# dc25-darknet-dialer-eaglev8_1.net
KiCad netlist of a schematic drawn in EAGLE
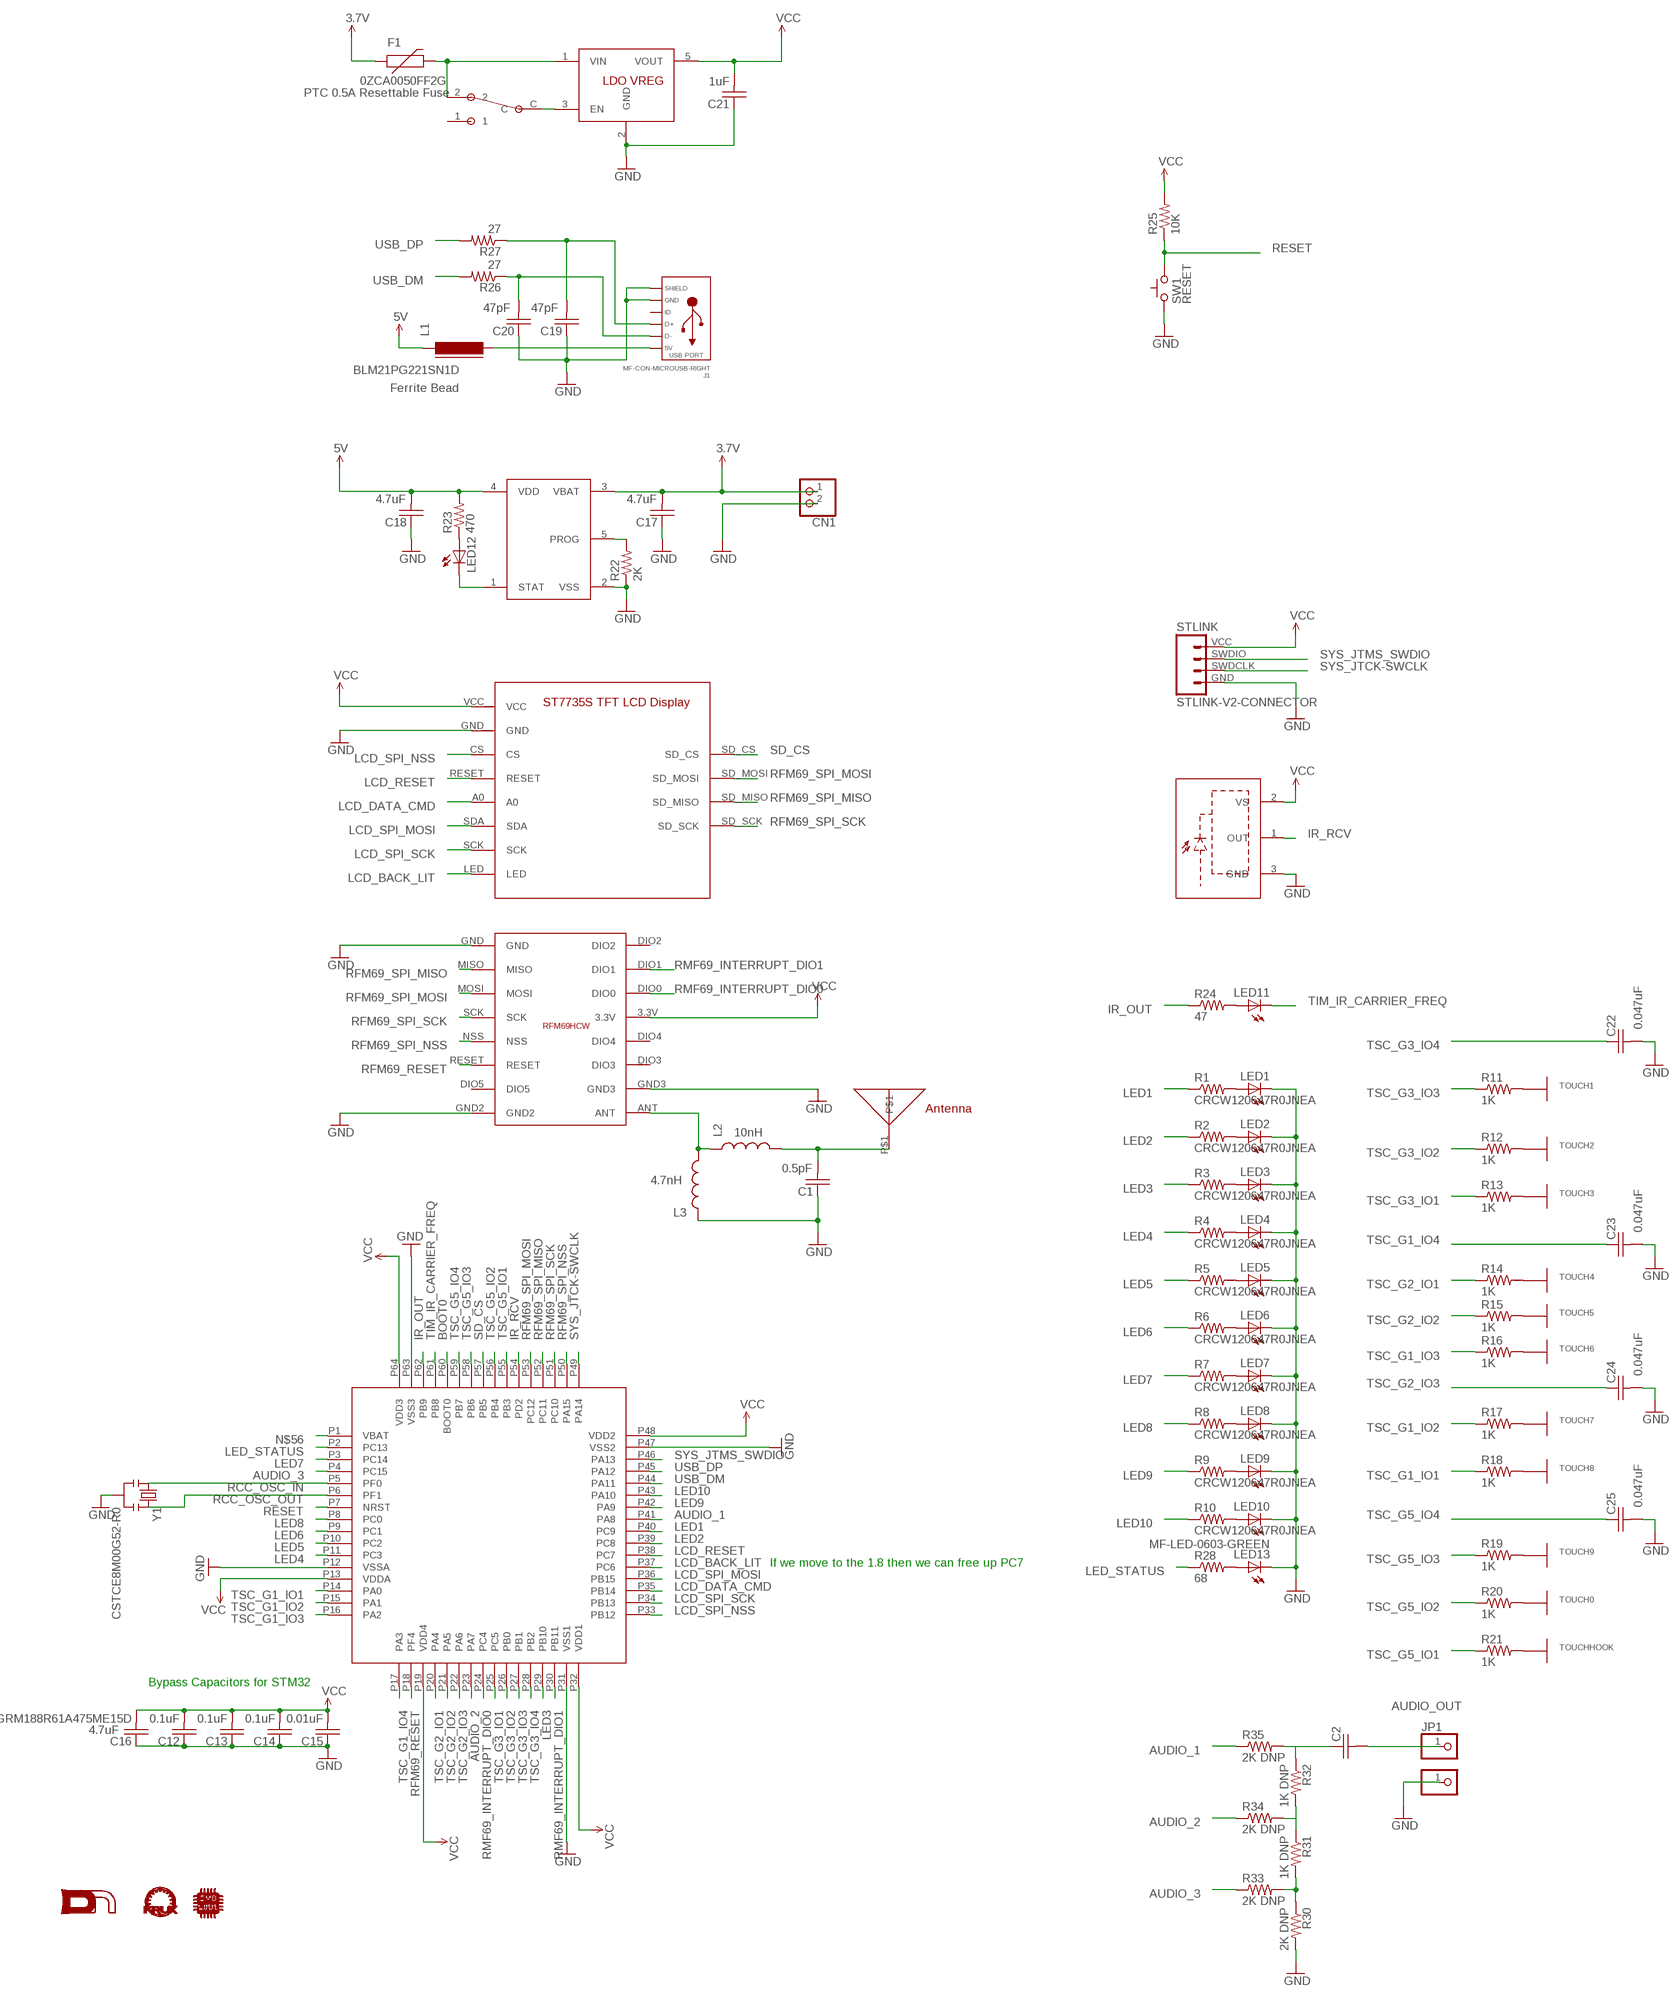
[diagram p0: schematic, sheet 1]

(export (version "E")
  (design (tool "Eeschema 10.0.6"))
  (components
    (comp (ref "C1")
      (value "251R14S0R5BV4T")
      (footprint "eagle-import:C0603")
      (libsource (lib "eagle-import") (part "C-USC0603"))
    )
    (comp (ref "C2")
      (value "10uF DNP")
      (footprint "eagle-import:C0603")
      (libsource (lib "eagle-import") (part "C-USC0603"))
    )
    (comp (ref "C12")
      (value "0.1uF")
      (footprint "eagle-import:C0603")
      (libsource (lib "eagle-import") (part "C-USC0603"))
    )
    (comp (ref "C13")
      (value "0.1uF")
      (footprint "eagle-import:C0603")
      (libsource (lib "eagle-import") (part "C-USC0603"))
    )
    (comp (ref "C14")
      (value "0.1uF")
      (footprint "eagle-import:C0603")
      (libsource (lib "eagle-import") (part "C-USC0603"))
    )
    (comp (ref "C15")
      (value "0.01uF")
      (footprint "eagle-import:C0603")
      (libsource (lib "eagle-import") (part "C-USC0603"))
    )
    (comp (ref "C16")
      (value "GRM188R61A475ME15D")
      (footprint "eagle-import:C0603")
      (libsource (lib "eagle-import") (part "C-USC0603"))
    )
    (comp (ref "C17")
      (value "GRM188R61A475ME15D")
      (footprint "eagle-import:C0603")
      (libsource (lib "eagle-import") (part "C-USC0603"))
    )
    (comp (ref "C18")
      (value "GRM188R61A475ME15D")
      (footprint "eagle-import:C0603")
      (libsource (lib "eagle-import") (part "C-USC0603"))
    )
    (comp (ref "C19")
      (value "C0603C470J3GACTU")
      (footprint "eagle-import:C0603")
      (libsource (lib "eagle-import") (part "C-USC0603"))
    )
    (comp (ref "C20")
      (value "C0603C470J3GACTU")
      (footprint "eagle-import:C0603")
      (libsource (lib "eagle-import") (part "C-USC0603"))
    )
    (comp (ref "C21")
      (value "1uF")
      (footprint "eagle-import:C0603")
      (libsource (lib "eagle-import") (part "C-USC0603"))
    )
    (comp (ref "C22")
      (value "C0603C473J3RACAUTO")
      (footprint "eagle-import:C0603")
      (libsource (lib "eagle-import") (part "C-USC0603"))
    )
    (comp (ref "C23")
      (value "C0603C473J3RACAUTO")
      (footprint "eagle-import:C0603")
      (libsource (lib "eagle-import") (part "C-USC0603"))
    )
    (comp (ref "C24")
      (value "C0603C473J3RACAUTO")
      (footprint "eagle-import:C0603")
      (libsource (lib "eagle-import") (part "C-USC0603"))
    )
    (comp (ref "C25")
      (value "C0603C473J3RACAUTO")
      (footprint "eagle-import:C0603")
      (libsource (lib "eagle-import") (part "C-USC0603"))
    )
    (comp (ref "CN1")
      (value "JST_2PIN-THM-RA")
      (footprint "eagle-import:JST-PH-2-THM-RA")
      (libsource (lib "eagle-import") (part "JST_2PIN-THM-RA"))
    )
    (comp (ref "F1")
      (value "0ZCA0050FF2G")
      (footprint "eagle-import:PTC-1206")
      (libsource (lib "eagle-import") (part "PTCSMD"))
    )
    (comp (ref "J1")
      (value "MF-CON-MICROUSB-RIGHT")
      (footprint "eagle-import:MICROUSB-RIGHT")
      (fields (field (name "HOUSEPART") "YES"))
      (libsource (lib "eagle-import") (part "USB_MICRO_RIGHT"))
    )
    (comp (ref "JP1")
      (value "PINHD-1X1CB")
      (footprint "eagle-import:1X01-CLEANBIG")
      (libsource (lib "eagle-import") (part "PINHD-1X1CB"))
    )
    (comp (ref "JP2")
      (value "PINHD-1X1CB")
      (footprint "eagle-import:1X01-CLEANBIG")
      (libsource (lib "eagle-import") (part "PINHD-1X1CB"))
    )
    (comp (ref "L1")
      (value "BLM21PG221SN1D")
      (footprint "eagle-import:FB603")
      (libsource (lib "eagle-import") (part "FERRITE-0603"))
    )
    (comp (ref "L2")
      (value "CI160808-10NJ")
      (footprint "eagle-import:0603")
      (libsource (lib "eagle-import") (part "INDUCTOR0603"))
    )
    (comp (ref "L3")
      (value "CI160808-4N7D")
      (footprint "eagle-import:0603")
      (libsource (lib "eagle-import") (part "INDUCTOR0603"))
    )
    (comp (ref "LED1")
      (value "LEDREVERSEMOUNT_NOPASTE")
      (footprint "eagle-import:GULLWING_LED_NOPASTE")
      (libsource (lib "eagle-import") (part "LEDREVERSEMOUNT_NOPASTE"))
    )
    (comp (ref "LED2")
      (value "LEDREVERSEMOUNT_NOPASTE")
      (footprint "eagle-import:GULLWING_LED_NOPASTE")
      (libsource (lib "eagle-import") (part "LEDREVERSEMOUNT_NOPASTE"))
    )
    (comp (ref "LED3")
      (value "LEDREVERSEMOUNT_NOPASTE")
      (footprint "eagle-import:GULLWING_LED_NOPASTE")
      (libsource (lib "eagle-import") (part "LEDREVERSEMOUNT_NOPASTE"))
    )
    (comp (ref "LED4")
      (value "LEDREVERSEMOUNT_NOPASTE")
      (footprint "eagle-import:GULLWING_LED_NOPASTE")
      (libsource (lib "eagle-import") (part "LEDREVERSEMOUNT_NOPASTE"))
    )
    (comp (ref "LED5")
      (value "LEDREVERSEMOUNT_NOPASTE")
      (footprint "eagle-import:GULLWING_LED_NOPASTE")
      (libsource (lib "eagle-import") (part "LEDREVERSEMOUNT_NOPASTE"))
    )
    (comp (ref "LED6")
      (value "LEDREVERSEMOUNT_NOPASTE")
      (footprint "eagle-import:GULLWING_LED_NOPASTE")
      (libsource (lib "eagle-import") (part "LEDREVERSEMOUNT_NOPASTE"))
    )
    (comp (ref "LED7")
      (value "LEDREVERSEMOUNT_NOPASTE")
      (footprint "eagle-import:GULLWING_LED_NOPASTE")
      (libsource (lib "eagle-import") (part "LEDREVERSEMOUNT_NOPASTE"))
    )
    (comp (ref "LED8")
      (value "LEDREVERSEMOUNT_NOPASTE")
      (footprint "eagle-import:GULLWING_LED_NOPASTE")
      (libsource (lib "eagle-import") (part "LEDREVERSEMOUNT_NOPASTE"))
    )
    (comp (ref "LED9")
      (value "LEDREVERSEMOUNT_NOPASTE")
      (footprint "eagle-import:GULLWING_LED_NOPASTE")
      (libsource (lib "eagle-import") (part "LEDREVERSEMOUNT_NOPASTE"))
    )
    (comp (ref "LED10")
      (value "LEDREVERSEMOUNT_NOPASTE")
      (footprint "eagle-import:GULLWING_LED_NOPASTE")
      (libsource (lib "eagle-import") (part "LEDREVERSEMOUNT_NOPASTE"))
    )
    (comp (ref "LED11")
      (value "LED5MM")
      (footprint "eagle-import:LED5MM")
      (libsource (lib "eagle-import") (part "LED5MM"))
    )
    (comp (ref "LED12")
      (value "MF-LED-0603-GREEN")
      (footprint "eagle-import:LED-0603")
      (libsource (lib "eagle-import") (part "LED0603"))
    )
    (comp (ref "LED13")
      (value "MF-LED-0603-GREEN")
      (footprint "eagle-import:LED-0603")
      (libsource (lib "eagle-import") (part "LED0603"))
    )
    (comp (ref "R1")
      (value "CRCW120647R0JNEA")
      (footprint "eagle-import:1206")
      (libsource (lib "eagle-import") (part "RESISTOR1206"))
    )
    (comp (ref "R2")
      (value "CRCW120647R0JNEA")
      (footprint "eagle-import:1206")
      (libsource (lib "eagle-import") (part "RESISTOR1206"))
    )
    (comp (ref "R3")
      (value "CRCW120647R0JNEA")
      (footprint "eagle-import:1206")
      (libsource (lib "eagle-import") (part "RESISTOR1206"))
    )
    (comp (ref "R4")
      (value "CRCW120647R0JNEA")
      (footprint "eagle-import:1206")
      (libsource (lib "eagle-import") (part "RESISTOR1206"))
    )
    (comp (ref "R5")
      (value "CRCW120647R0JNEA")
      (footprint "eagle-import:1206")
      (libsource (lib "eagle-import") (part "RESISTOR1206"))
    )
    (comp (ref "R6")
      (value "CRCW120647R0JNEA")
      (footprint "eagle-import:1206")
      (libsource (lib "eagle-import") (part "RESISTOR1206"))
    )
    (comp (ref "R7")
      (value "CRCW120647R0JNEA")
      (footprint "eagle-import:1206")
      (libsource (lib "eagle-import") (part "RESISTOR1206"))
    )
    (comp (ref "R8")
      (value "CRCW120647R0JNEA")
      (footprint "eagle-import:1206")
      (libsource (lib "eagle-import") (part "RESISTOR1206"))
    )
    (comp (ref "R9")
      (value "CRCW120647R0JNEA")
      (footprint "eagle-import:1206")
      (libsource (lib "eagle-import") (part "RESISTOR1206"))
    )
    (comp (ref "R10")
      (value "CRCW120647R0JNEA")
      (footprint "eagle-import:1206")
      (libsource (lib "eagle-import") (part "RESISTOR1206"))
    )
    (comp (ref "R11")
      (value "1K")
      (footprint "eagle-import:0603-RES")
      (libsource (lib "eagle-import") (part "RESISTOR0603-RES"))
    )
    (comp (ref "R12")
      (value "1K")
      (footprint "eagle-import:0603-RES")
      (libsource (lib "eagle-import") (part "RESISTOR0603-RES"))
    )
    (comp (ref "R13")
      (value "1K")
      (footprint "eagle-import:0603-RES")
      (libsource (lib "eagle-import") (part "RESISTOR0603-RES"))
    )
    (comp (ref "R14")
      (value "1K")
      (footprint "eagle-import:0603-RES")
      (libsource (lib "eagle-import") (part "RESISTOR0603-RES"))
    )
    (comp (ref "R15")
      (value "1K")
      (footprint "eagle-import:0603-RES")
      (libsource (lib "eagle-import") (part "RESISTOR0603-RES"))
    )
    (comp (ref "R16")
      (value "1K")
      (footprint "eagle-import:0603-RES")
      (libsource (lib "eagle-import") (part "RESISTOR0603-RES"))
    )
    (comp (ref "R17")
      (value "1K")
      (footprint "eagle-import:0603-RES")
      (libsource (lib "eagle-import") (part "RESISTOR0603-RES"))
    )
    (comp (ref "R18")
      (value "1K")
      (footprint "eagle-import:0603-RES")
      (libsource (lib "eagle-import") (part "RESISTOR0603-RES"))
    )
    (comp (ref "R19")
      (value "1K")
      (footprint "eagle-import:0603-RES")
      (libsource (lib "eagle-import") (part "RESISTOR0603-RES"))
    )
    (comp (ref "R20")
      (value "1K")
      (footprint "eagle-import:0603-RES")
      (libsource (lib "eagle-import") (part "RESISTOR0603-RES"))
    )
    (comp (ref "R21")
      (value "1K")
      (footprint "eagle-import:0603-RES")
      (libsource (lib "eagle-import") (part "RESISTOR0603-RES"))
    )
    (comp (ref "R22")
      (value "2K")
      (footprint "eagle-import:0603-RES")
      (libsource (lib "eagle-import") (part "RESISTOR0603-RES"))
    )
    (comp (ref "R23")
      (value "470")
      (footprint "eagle-import:0603-RES")
      (libsource (lib "eagle-import") (part "RESISTOR0603-RES"))
    )
    (comp (ref "R24")
      (value "47")
      (footprint "eagle-import:0207_7")
      (libsource (lib "eagle-import") (part "R-US_0207/7"))
    )
    (comp (ref "R25")
      (value "10K")
      (footprint "eagle-import:0603-RES")
      (libsource (lib "eagle-import") (part "RESISTOR0603-RES"))
    )
    (comp (ref "R26")
      (value "27")
      (footprint "eagle-import:0603-RES")
      (libsource (lib "eagle-import") (part "RESISTOR0603-RES"))
    )
    (comp (ref "R27")
      (value "27")
      (footprint "eagle-import:0603-RES")
      (libsource (lib "eagle-import") (part "RESISTOR0603-RES"))
    )
    (comp (ref "R28")
      (value "68")
      (footprint "eagle-import:0603-RES")
      (libsource (lib "eagle-import") (part "RESISTOR0603-RES"))
    )
    (comp (ref "R30")
      (value "2K DNP")
      (footprint "eagle-import:0603-RES")
      (libsource (lib "eagle-import") (part "RESISTOR0603-RES"))
    )
    (comp (ref "R31")
      (value "1K DNP")
      (footprint "eagle-import:0603-RES")
      (libsource (lib "eagle-import") (part "RESISTOR0603-RES"))
    )
    (comp (ref "R32")
      (value "1K DNP")
      (footprint "eagle-import:0603-RES")
      (libsource (lib "eagle-import") (part "RESISTOR0603-RES"))
    )
    (comp (ref "R33")
      (value "2K DNP")
      (footprint "eagle-import:0603-RES")
      (libsource (lib "eagle-import") (part "RESISTOR0603-RES"))
    )
    (comp (ref "R34")
      (value "2K DNP")
      (footprint "eagle-import:0603-RES")
      (libsource (lib "eagle-import") (part "RESISTOR0603-RES"))
    )
    (comp (ref "R35")
      (value "2K DNP")
      (footprint "eagle-import:0603-RES")
      (libsource (lib "eagle-import") (part "RESISTOR0603-RES"))
    )
    (comp (ref "STLINK")
      (value "STLINK-V2-CONNECTOR")
      (footprint "eagle-import:1X04")
      (libsource (lib "eagle-import") (part "STLINK-V2-CONNECTOR"))
    )
    (comp (ref "SW1")
      (value "RESET")
      (footprint "eagle-import:TACTILE-2PIN-NARROW")
      (libsource (lib "eagle-import") (part "SWITCH_TACTILETACTILE-2PIN-NARROW"))
    )
    (comp (ref "TOUCH0")
      (value "CAP_TOUCH0")
      (footprint "eagle-import:CAP_TOUCH_PAD_0")
      (libsource (lib "eagle-import") (part "CAP_TOUCH0"))
    )
    (comp (ref "TOUCH1")
      (value "CAP_TOUCH1")
      (footprint "eagle-import:CAP_TOUCH_PAD_1")
      (libsource (lib "eagle-import") (part "CAP_TOUCH1"))
    )
    (comp (ref "TOUCH2")
      (value "CAP_TOUCH2")
      (footprint "eagle-import:CAP_TOUCH_PAD_2")
      (libsource (lib "eagle-import") (part "CAP_TOUCH2"))
    )
    (comp (ref "TOUCH3")
      (value "CAP_TOUCH3")
      (footprint "eagle-import:CAP_TOUCH_PAD_3")
      (libsource (lib "eagle-import") (part "CAP_TOUCH3"))
    )
    (comp (ref "TOUCH4")
      (value "CAP_TOUCH4")
      (footprint "eagle-import:CAP_TOUCH_PAD_4")
      (libsource (lib "eagle-import") (part "CAP_TOUCH4"))
    )
    (comp (ref "TOUCH5")
      (value "CAP_TOUCH5")
      (footprint "eagle-import:CAP_TOUCH_PAD_5")
      (libsource (lib "eagle-import") (part "CAP_TOUCH5"))
    )
    (comp (ref "TOUCH6")
      (value "CAP_TOUCH6")
      (footprint "eagle-import:CAP_TOUCH_PAD_6")
      (libsource (lib "eagle-import") (part "CAP_TOUCH6"))
    )
    (comp (ref "TOUCH7")
      (value "CAP_TOUCH7")
      (footprint "eagle-import:CAP_TOUCH_PAD_7")
      (libsource (lib "eagle-import") (part "CAP_TOUCH7"))
    )
    (comp (ref "TOUCH8")
      (value "CAP_TOUCH8")
      (footprint "eagle-import:CAP_TOUCH_PAD_8")
      (libsource (lib "eagle-import") (part "CAP_TOUCH8"))
    )
    (comp (ref "TOUCH9")
      (value "CAP_TOUCH9")
      (footprint "eagle-import:CAP_TOUCH_PAD_9")
      (libsource (lib "eagle-import") (part "CAP_TOUCH9"))
    )
    (comp (ref "TOUCHHOOK")
      (value "CAP_TOUCHHOOK")
      (footprint "eagle-import:CAP_TOUCH_PAD_HOOK")
      (libsource (lib "eagle-import") (part "CAP_TOUCHHOOK"))
    )
    (comp (ref "U$1")
      (value "DN_LOGO")
      (footprint "eagle-import:DN_LOGO")
      (libsource (lib "eagle-import") (part "DN_LOGO"))
    )
    (comp (ref "U$2")
      (value "STM32F302RBT6")
      (footprint "eagle-import:LQFP64")
      (libsource (lib "eagle-import") (part "STM32F302XC"))
    )
    (comp (ref "U$11")
      (value "SWITCH_SPDT")
      (footprint "eagle-import:SPDT_SSAJ120100")
      (libsource (lib "eagle-import") (part "SWITCH_SPDT"))
    )
    (comp (ref "U$12")
      (value "KRUX_LOGO")
      (footprint "eagle-import:KRUX_LOGO")
      (libsource (lib "eagle-import") (part "KRUX_LOGO"))
    )
    (comp (ref "U$15")
      (value "RFM69HCWRFM69HCWSMDNOPASTE")
      (footprint "eagle-import:16PIN-PCB-SMD-NOPASTE")
      (libsource (lib "eagle-import") (part "RFM69HCWRFM69HCWSMDNOPASTE"))
    )
    (comp (ref "U$21")
      (value "0915AT43A0026E")
      (footprint "eagle-import:CHIP_ANTENNA_1.8X8MM")
      (libsource (lib "eagle-import") (part "CHIP_ANTENNA"))
    )
    (comp (ref "U$22")
      (value "ST7735S_LCD_MODULE")
      (footprint "eagle-import:ST7735S_LCD_DISPLAY")
      (libsource (lib "eagle-import") (part "ST7735S_LCD_MODULE"))
    )
    (comp (ref "U$23")
      (value "CMD_C0DE_LOGO")
      (footprint "eagle-import:CMD_C0DE_LOGO")
      (libsource (lib "eagle-import") (part "CMD_C0DE_LOGO"))
    )
    (comp (ref "U1")
      (value "BU33SD5WG-TR")
      (footprint "eagle-import:SOT23-5")
      (libsource (lib "eagle-import") (part "TLV702"))
    )
    (comp (ref "U2")
      (value "MCP73831T-5ACI/OT")
      (footprint "eagle-import:SOT23-5")
      (libsource (lib "eagle-import") (part "DS21984E"))
    )
    (comp (ref "U3")
      (value "SOP22FLAT")
      (footprint "eagle-import:IR-MODULE_FLAT")
      (libsource (lib "eagle-import") (part "SOP22FLAT"))
    )
    (comp (ref "Y1")
      (value "CSTCE8M00G52-R0")
      (footprint "eagle-import:RESONATOR-SMD")
      (libsource (lib "eagle-import") (part "RESONATORSMD"))
    )
  )
  (nets
    (net (code "1") (name "/AUDIO_1") (class "Default")
      (node (ref "R35") (pin "1") (pinfunction "1_1") (pintype "passive"))
      (node (ref "U$2") (pin "P41") (pinfunction "PA8_P41") (pintype "bidirectional"))
    )
    (net (code "2") (name "/AUDIO_2") (class "Default")
      (node (ref "R34") (pin "1") (pinfunction "1_1") (pintype "passive"))
      (node (ref "U$2") (pin "P23") (pinfunction "PA7_P23") (pintype "bidirectional"))
    )
    (net (code "3") (name "/AUDIO_3") (class "Default")
      (node (ref "R33") (pin "1") (pinfunction "1_1") (pintype "passive"))
      (node (ref "U$2") (pin "P4") (pinfunction "PC15_P4") (pintype "bidirectional"))
    )
    (net (code "4") (name "/AUDIO_OUT") (class "Default")
      (node (ref "C2") (pin "2") (pinfunction "2_2") (pintype "passive"))
      (node (ref "JP1") (pin "1") (pinfunction "1_1") (pintype "passive"))
    )
    (net (code "5") (name "/BOOT0") (class "Default")
      (node (ref "U$2") (pin "P60") (pinfunction "BOOT0_P60") (pintype "bidirectional"))
    )
    (net (code "6") (name "/IR_OUT") (class "Default")
      (node (ref "R24") (pin "1") (pinfunction "1_1") (pintype "passive"))
      (node (ref "U$2") (pin "P62") (pinfunction "PB9_P62") (pintype "bidirectional"))
    )
    (net (code "7") (name "/IR_RCV") (class "Default")
      (node (ref "U$2") (pin "P54") (pinfunction "PD2_P54") (pintype "bidirectional"))
      (node (ref "U3") (pin "1") (pinfunction "OUT_1") (pintype "bidirectional"))
    )
    (net (code "8") (name "/LCD_BACK_LIT") (class "Default")
      (node (ref "U$2") (pin "P37") (pinfunction "PC6_P37") (pintype "bidirectional"))
      (node (ref "U$22") (pin "LED") (pinfunction "LED_LED") (pintype "bidirectional"))
    )
    (net (code "9") (name "/LCD_DATA_CMD") (class "Default")
      (node (ref "U$2") (pin "P35") (pinfunction "PB14_P35") (pintype "bidirectional"))
      (node (ref "U$22") (pin "A0") (pinfunction "A0_A0") (pintype "bidirectional"))
    )
    (net (code "10") (name "/LCD_RESET") (class "Default")
      (node (ref "U$2") (pin "P38") (pinfunction "PC7_P38") (pintype "bidirectional"))
      (node (ref "U$22") (pin "RESET") (pinfunction "RESET_RESET") (pintype "bidirectional"))
    )
    (net (code "11") (name "/LCD_SPI_MOSI") (class "Default")
      (node (ref "U$2") (pin "P36") (pinfunction "PB15_P36") (pintype "bidirectional"))
      (node (ref "U$22") (pin "SDA") (pinfunction "SDA_SDA") (pintype "bidirectional"))
    )
    (net (code "12") (name "/LCD_SPI_NSS") (class "Default")
      (node (ref "U$2") (pin "P33") (pinfunction "PB12_P33") (pintype "bidirectional"))
      (node (ref "U$22") (pin "CS") (pinfunction "CS_CS") (pintype "bidirectional"))
    )
    (net (code "13") (name "/LCD_SPI_SCK") (class "Default")
      (node (ref "U$2") (pin "P34") (pinfunction "PB13_P34") (pintype "bidirectional"))
      (node (ref "U$22") (pin "SCK") (pinfunction "SCK_SCK") (pintype "bidirectional"))
    )
    (net (code "14") (name "/LED1") (class "Default")
      (node (ref "R1") (pin "1") (pinfunction "1_1") (pintype "passive"))
      (node (ref "U$2") (pin "P40") (pinfunction "PC9_P40") (pintype "bidirectional"))
    )
    (net (code "15") (name "/LED2") (class "Default")
      (node (ref "R2") (pin "1") (pinfunction "1_1") (pintype "passive"))
      (node (ref "U$2") (pin "P39") (pinfunction "PC8_P39") (pintype "bidirectional"))
    )
    (net (code "16") (name "/LED3") (class "Default")
      (node (ref "R3") (pin "1") (pinfunction "1_1") (pintype "passive"))
      (node (ref "U$2") (pin "P29") (pinfunction "PB10_P29") (pintype "bidirectional"))
    )
    (net (code "17") (name "/LED4") (class "Default")
      (node (ref "R4") (pin "1") (pinfunction "1_1") (pintype "passive"))
      (node (ref "U$2") (pin "P11") (pinfunction "PC3_P11") (pintype "bidirectional"))
    )
    (net (code "18") (name "/LED5") (class "Default")
      (node (ref "R5") (pin "1") (pinfunction "1_1") (pintype "passive"))
      (node (ref "U$2") (pin "P10") (pinfunction "PC2_P10") (pintype "bidirectional"))
    )
    (net (code "19") (name "/LED6") (class "Default")
      (node (ref "R6") (pin "1") (pinfunction "1_1") (pintype "passive"))
      (node (ref "U$2") (pin "P9") (pinfunction "PC1_P9") (pintype "bidirectional"))
    )
    (net (code "20") (name "/LED7") (class "Default")
      (node (ref "R7") (pin "1") (pinfunction "1_1") (pintype "passive"))
      (node (ref "U$2") (pin "P3") (pinfunction "PC14_P3") (pintype "bidirectional"))
    )
    (net (code "21") (name "/LED8") (class "Default")
      (node (ref "R8") (pin "1") (pinfunction "1_1") (pintype "passive"))
      (node (ref "U$2") (pin "P8") (pinfunction "PC0_P8") (pintype "bidirectional"))
    )
    (net (code "22") (name "/LED9") (class "Default")
      (node (ref "R9") (pin "1") (pinfunction "1_1") (pintype "passive"))
      (node (ref "U$2") (pin "P42") (pinfunction "PA9_P42") (pintype "bidirectional"))
    )
    (net (code "23") (name "/LED10") (class "Default")
      (node (ref "R10") (pin "1") (pinfunction "1_1") (pintype "passive"))
      (node (ref "U$2") (pin "P43") (pinfunction "PA10_P43") (pintype "bidirectional"))
    )
    (net (code "24") (name "/LED_STATUS") (class "Default")
      (node (ref "R28") (pin "1") (pinfunction "1_1") (pintype "passive"))
      (node (ref "U$2") (pin "P2") (pinfunction "PC13_P2") (pintype "bidirectional"))
    )
    (net (code "25") (name "/N$56") (class "Default")
      (node (ref "U$2") (pin "P1") (pinfunction "VBAT_P1") (pintype "bidirectional"))
    )
    (net (code "26") (name "/RCC_OSC_IN") (class "Default")
      (node (ref "U$2") (pin "P5") (pinfunction "PF0_P5") (pintype "bidirectional"))
      (node (ref "Y1") (pin "1") (pinfunction "1_1") (pintype "passive"))
    )
    (net (code "27") (name "/RCC_OSC_OUT") (class "Default")
      (node (ref "U$2") (pin "P6") (pinfunction "PF1_P6") (pintype "bidirectional"))
      (node (ref "Y1") (pin "3") (pinfunction "3_3") (pintype "passive"))
    )
    (net (code "28") (name "/RESET") (class "Default")
      (node (ref "R25") (pin "1") (pinfunction "1_1") (pintype "passive"))
      (node (ref "SW1") (pin "P$1") (pinfunction "A_P$1") (pintype "passive"))
      (node (ref "U$2") (pin "P7") (pinfunction "NRST_P7") (pintype "bidirectional"))
    )
    (net (code "29") (name "/RFM69_RESET") (class "Default")
      (node (ref "U$15") (pin "RESET") (pinfunction "RESET_RESET") (pintype "bidirectional"))
      (node (ref "U$2") (pin "P18") (pinfunction "PF4_P18") (pintype "bidirectional"))
    )
    (net (code "30") (name "/RFM69_SPI_MISO") (class "Default")
      (node (ref "U$15") (pin "MISO") (pinfunction "MISO_MISO") (pintype "bidirectional"))
      (node (ref "U$2") (pin "P52") (pinfunction "PC11_P52") (pintype "bidirectional"))
      (node (ref "U$22") (pin "SD_MISO") (pinfunction "SD_MISO_SD_MISO") (pintype "bidirectional"))
    )
    (net (code "31") (name "/RFM69_SPI_MOSI") (class "Default")
      (node (ref "U$15") (pin "MOSI") (pinfunction "MOSI_MOSI") (pintype "bidirectional"))
      (node (ref "U$2") (pin "P53") (pinfunction "PC12_P53") (pintype "bidirectional"))
      (node (ref "U$22") (pin "SD_MOSI") (pinfunction "SD_MOSI_SD_MOSI") (pintype "bidirectional"))
    )
    (net (code "32") (name "/RFM69_SPI_NSS") (class "Default")
      (node (ref "U$15") (pin "NSS") (pinfunction "NSS_NSS") (pintype "bidirectional"))
      (node (ref "U$2") (pin "P50") (pinfunction "PA15_P50") (pintype "bidirectional"))
    )
    (net (code "33") (name "/RFM69_SPI_SCK") (class "Default")
      (node (ref "U$15") (pin "SCK") (pinfunction "SCK_SCK") (pintype "bidirectional"))
      (node (ref "U$2") (pin "P51") (pinfunction "PC10_P51") (pintype "bidirectional"))
      (node (ref "U$22") (pin "SD_SCK") (pinfunction "SD_SCK_SD_SCK") (pintype "bidirectional"))
    )
    (net (code "34") (name "/RMF69_INTERRUPT_DIO0") (class "Default")
      (node (ref "U$15") (pin "DIO0") (pinfunction "DIO0_DIO0") (pintype "bidirectional"))
      (node (ref "U$2") (pin "P24") (pinfunction "PC4_P24") (pintype "bidirectional"))
    )
    (net (code "35") (name "/RMF69_INTERRUPT_DIO1") (class "Default")
      (node (ref "U$15") (pin "DIO1") (pinfunction "DIO1_DIO1") (pintype "bidirectional"))
      (node (ref "U$2") (pin "P30") (pinfunction "PB11_P30") (pintype "bidirectional"))
    )
    (net (code "36") (name "/SD_CS") (class "Default")
      (node (ref "U$2") (pin "P57") (pinfunction "PB5_P57") (pintype "bidirectional"))
      (node (ref "U$22") (pin "SD_CS") (pinfunction "SD_CS_SD_CS") (pintype "bidirectional"))
    )
    (net (code "37") (name "/SYS_JTCK-SWCLK") (class "Default")
      (node (ref "STLINK") (pin "SWDCLK") (pinfunction "SWDCLK_SWDCLK") (pintype "input"))
      (node (ref "U$2") (pin "P49") (pinfunction "PA14_P49") (pintype "bidirectional"))
    )
    (net (code "38") (name "/SYS_JTMS_SWDIO") (class "Default")
      (node (ref "STLINK") (pin "SWDIO") (pinfunction "SWDIO_SWDIO") (pintype "bidirectional"))
      (node (ref "U$2") (pin "P46") (pinfunction "PA13_P46") (pintype "bidirectional"))
    )
    (net (code "39") (name "/TIM_IR_CARRIER_FREQ") (class "Default")
      (node (ref "LED11") (pin "K") (pinfunction "C_K") (pintype "output"))
      (node (ref "U$2") (pin "P61") (pinfunction "PB8_P61") (pintype "bidirectional"))
    )
    (net (code "40") (name "/TSC_G1_IO1") (class "Default")
      (node (ref "R18") (pin "1") (pinfunction "1_1") (pintype "passive"))
      (node (ref "U$2") (pin "P14") (pinfunction "PA0_P14") (pintype "bidirectional"))
    )
    (net (code "41") (name "/TSC_G1_IO2") (class "Default")
      (node (ref "R17") (pin "1") (pinfunction "1_1") (pintype "passive"))
      (node (ref "U$2") (pin "P15") (pinfunction "PA1_P15") (pintype "bidirectional"))
    )
    (net (code "42") (name "/TSC_G1_IO3") (class "Default")
      (node (ref "R16") (pin "1") (pinfunction "1_1") (pintype "passive"))
      (node (ref "U$2") (pin "P16") (pinfunction "PA2_P16") (pintype "bidirectional"))
    )
    (net (code "43") (name "/TSC_G1_IO4") (class "Default")
      (node (ref "C23") (pin "1") (pinfunction "1_1") (pintype "passive"))
      (node (ref "U$2") (pin "P17") (pinfunction "PA3_P17") (pintype "bidirectional"))
    )
    (net (code "44") (name "/TSC_G2_IO1") (class "Default")
      (node (ref "R14") (pin "1") (pinfunction "1_1") (pintype "passive"))
      (node (ref "U$2") (pin "P20") (pinfunction "PA4_P20") (pintype "bidirectional"))
    )
    (net (code "45") (name "/TSC_G2_IO2") (class "Default")
      (node (ref "R15") (pin "1") (pinfunction "1_1") (pintype "passive"))
      (node (ref "U$2") (pin "P21") (pinfunction "PA5_P21") (pintype "bidirectional"))
    )
    (net (code "46") (name "/TSC_G2_IO3") (class "Default")
      (node (ref "C24") (pin "1") (pinfunction "1_1") (pintype "passive"))
      (node (ref "U$2") (pin "P22") (pinfunction "PA6_P22") (pintype "bidirectional"))
    )
    (net (code "47") (name "/TSC_G3_IO1") (class "Default")
      (node (ref "R13") (pin "1") (pinfunction "1_1") (pintype "passive"))
      (node (ref "U$2") (pin "P25") (pinfunction "PC5_P25") (pintype "bidirectional"))
    )
    (net (code "48") (name "/TSC_G3_IO2") (class "Default")
      (node (ref "R12") (pin "1") (pinfunction "1_1") (pintype "passive"))
      (node (ref "U$2") (pin "P26") (pinfunction "PB0_P26") (pintype "bidirectional"))
    )
    (net (code "49") (name "/TSC_G3_IO3") (class "Default")
      (node (ref "R11") (pin "1") (pinfunction "1_1") (pintype "passive"))
      (node (ref "U$2") (pin "P27") (pinfunction "PB1_P27") (pintype "bidirectional"))
    )
    (net (code "50") (name "/TSC_G3_IO4") (class "Default")
      (node (ref "C22") (pin "1") (pinfunction "1_1") (pintype "passive"))
      (node (ref "U$2") (pin "P28") (pinfunction "PB2_P28") (pintype "bidirectional"))
    )
    (net (code "51") (name "/TSC_G5_IO1") (class "Default")
      (node (ref "R21") (pin "1") (pinfunction "1_1") (pintype "passive"))
      (node (ref "U$2") (pin "P55") (pinfunction "PB3_P55") (pintype "bidirectional"))
    )
    (net (code "52") (name "/TSC_G5_IO2") (class "Default")
      (node (ref "R20") (pin "1") (pinfunction "1_1") (pintype "passive"))
      (node (ref "U$2") (pin "P56") (pinfunction "PB4_P56") (pintype "bidirectional"))
    )
    (net (code "53") (name "/TSC_G5_IO3") (class "Default")
      (node (ref "R19") (pin "1") (pinfunction "1_1") (pintype "passive"))
      (node (ref "U$2") (pin "P58") (pinfunction "PB6_P58") (pintype "bidirectional"))
    )
    (net (code "54") (name "/TSC_G5_IO4") (class "Default")
      (node (ref "C25") (pin "1") (pinfunction "1_1") (pintype "passive"))
      (node (ref "U$2") (pin "P59") (pinfunction "PB7_P59") (pintype "bidirectional"))
    )
    (net (code "55") (name "/USB_DM") (class "Default")
      (node (ref "R26") (pin "2") (pinfunction "2_2") (pintype "passive"))
      (node (ref "U$2") (pin "P44") (pinfunction "PA11_P44") (pintype "bidirectional"))
    )
    (net (code "56") (name "/USB_DP") (class "Default")
      (node (ref "R27") (pin "2") (pinfunction "2_2") (pintype "passive"))
      (node (ref "U$2") (pin "P45") (pinfunction "PA12_P45") (pintype "bidirectional"))
    )
    (net (code "57") (name "3.7V") (class "Default")
      (node (ref "C17") (pin "2") (pinfunction "2_2") (pintype "passive"))
      (node (ref "CN1") (pin "1") (pinfunction "2_1") (pintype "passive"))
      (node (ref "F1") (pin "1") (pinfunction "1_1") (pintype "bidirectional"))
      (node (ref "U2") (pin "3") (pinfunction "VBAT_3") (pintype "bidirectional"))
    )
    (net (code "58") (name "5V") (class "Default")
      (node (ref "C18") (pin "2") (pinfunction "2_2") (pintype "passive"))
      (node (ref "L1") (pin "1") (pinfunction "1_1") (pintype "passive"))
      (node (ref "R23") (pin "2") (pinfunction "2_2") (pintype "passive"))
      (node (ref "U2") (pin "4") (pinfunction "VDD_4") (pintype "bidirectional"))
    )
    (net (code "59") (name "GND") (class "Default")
      (node (ref "C1") (pin "1") (pinfunction "1_1") (pintype "passive"))
      (node (ref "C12") (pin "1") (pinfunction "1_1") (pintype "passive"))
      (node (ref "C13") (pin "1") (pinfunction "1_1") (pintype "passive"))
      (node (ref "C14") (pin "1") (pinfunction "1_1") (pintype "passive"))
      (node (ref "C15") (pin "1") (pinfunction "1_1") (pintype "passive"))
      (node (ref "C16") (pin "1") (pinfunction "1_1") (pintype "passive"))
      (node (ref "C17") (pin "1") (pinfunction "1_1") (pintype "passive"))
      (node (ref "C18") (pin "1") (pinfunction "1_1") (pintype "passive"))
      (node (ref "C19") (pin "1") (pinfunction "1_1") (pintype "passive"))
      (node (ref "C20") (pin "1") (pinfunction "1_1") (pintype "passive"))
      (node (ref "C21") (pin "1") (pinfunction "1_1") (pintype "passive"))
      (node (ref "C22") (pin "2") (pinfunction "2_2") (pintype "passive"))
      (node (ref "C23") (pin "2") (pinfunction "2_2") (pintype "passive"))
      (node (ref "C24") (pin "2") (pinfunction "2_2") (pintype "passive"))
      (node (ref "C25") (pin "2") (pinfunction "2_2") (pintype "passive"))
      (node (ref "CN1") (pin "2") (pinfunction "1_2") (pintype "passive"))
      (node (ref "J1") (pin "5") (pinfunction "GND_5") (pintype "power_in"))
      (node (ref "J1") (pin "S1") (pinfunction "SLD_S1") (pintype "power_in"))
      (node (ref "J1") (pin "S2") (pinfunction "SLD_S2") (pintype "power_in"))
      (node (ref "J1") (pin "S3") (pinfunction "SLD_S3") (pintype "power_in"))
      (node (ref "J1") (pin "S4") (pinfunction "SLD_S4") (pintype "power_in"))
      (node (ref "J1") (pin "S5") (pinfunction "SLD_S5") (pintype "power_in"))
      (node (ref "J1") (pin "S6") (pinfunction "SLD_S6") (pintype "power_in"))
      (node (ref "JP2") (pin "1") (pinfunction "1_1") (pintype "passive"))
      (node (ref "L3") (pin "1") (pinfunction "1_1") (pintype "passive"))
      (node (ref "LED1") (pin "C") (pinfunction "C_C") (pintype "output"))
      (node (ref "LED10") (pin "C") (pinfunction "C_C") (pintype "output"))
      (node (ref "LED13") (pin "C") (pinfunction "C_C") (pintype "output"))
      (node (ref "LED2") (pin "C") (pinfunction "C_C") (pintype "output"))
      (node (ref "LED3") (pin "C") (pinfunction "C_C") (pintype "output"))
      (node (ref "LED4") (pin "C") (pinfunction "C_C") (pintype "output"))
      (node (ref "LED5") (pin "C") (pinfunction "C_C") (pintype "output"))
      (node (ref "LED6") (pin "C") (pinfunction "C_C") (pintype "output"))
      (node (ref "LED7") (pin "C") (pinfunction "C_C") (pintype "output"))
      (node (ref "LED8") (pin "C") (pinfunction "C_C") (pintype "output"))
      (node (ref "LED9") (pin "C") (pinfunction "C_C") (pintype "output"))
      (node (ref "R22") (pin "1") (pinfunction "1_1") (pintype "passive"))
      (node (ref "R30") (pin "2") (pinfunction "2_2") (pintype "passive"))
      (node (ref "STLINK") (pin "GND") (pinfunction "GND_GND") (pintype "power_in"))
      (node (ref "SW1") (pin "P$2") (pinfunction "C_P$2") (pintype "passive"))
      (node (ref "U$15") (pin "GND") (pinfunction "GND_GND") (pintype "bidirectional"))
      (node (ref "U$15") (pin "GND2") (pinfunction "GND2_GND2") (pintype "bidirectional"))
      (node (ref "U$15") (pin "GND3") (pinfunction "GND3_GND3") (pintype "bidirectional"))
      (node (ref "U$2") (pin "P12") (pinfunction "VSSA_P12") (pintype "bidirectional"))
      (node (ref "U$2") (pin "P31") (pinfunction "VSS1_P31") (pintype "bidirectional"))
      (node (ref "U$2") (pin "P47") (pinfunction "VSS2_P47") (pintype "bidirectional"))
      (node (ref "U$2") (pin "P63") (pinfunction "VSS3_P63") (pintype "bidirectional"))
      (node (ref "U$22") (pin "GND") (pinfunction "GND_GND") (pintype "bidirectional"))
      (node (ref "U1") (pin "2") (pinfunction "GND_2") (pintype "bidirectional"))
      (node (ref "U2") (pin "2") (pinfunction "VSS_2") (pintype "bidirectional"))
      (node (ref "U3") (pin "3") (pinfunction "GND_3") (pintype "bidirectional"))
      (node (ref "Y1") (pin "2") (pinfunction "2_2") (pintype "passive"))
    )
    (net (code "60") (name "Net-(C1-Pad2)") (class "Default")
      (node (ref "C1") (pin "2") (pinfunction "2_2") (pintype "passive"))
      (node (ref "L2") (pin "2") (pinfunction "2_2") (pintype "passive"))
      (node (ref "U$21") (pin "P$1") (pinfunction "P$1_P$1") (pintype "bidirectional"))
    )
    (net (code "61") (name "Net-(C2-Pad1)") (class "Default")
      (node (ref "C2") (pin "1") (pinfunction "1_1") (pintype "passive"))
      (node (ref "R32") (pin "1") (pinfunction "1_1") (pintype "passive"))
      (node (ref "R35") (pin "2") (pinfunction "2_2") (pintype "passive"))
    )
    (net (code "62") (name "Net-(J1-5V)") (class "Default")
      (node (ref "J1") (pin "1") (pinfunction "5V_1") (pintype "power_in"))
      (node (ref "L1") (pin "2") (pinfunction "2_2") (pintype "passive"))
    )
    (net (code "63") (name "Net-(J1-D+)") (class "Default")
      (node (ref "C19") (pin "2") (pinfunction "2_2") (pintype "passive"))
      (node (ref "J1") (pin "3") (pinfunction "D+_3") (pintype "bidirectional"))
      (node (ref "R27") (pin "1") (pinfunction "1_1") (pintype "passive"))
    )
    (net (code "64") (name "Net-(J1-D-)") (class "Default")
      (node (ref "C20") (pin "2") (pinfunction "2_2") (pintype "passive"))
      (node (ref "J1") (pin "2") (pinfunction "D-_2") (pintype "bidirectional"))
      (node (ref "R26") (pin "1") (pinfunction "1_1") (pintype "passive"))
    )
    (net (code "65") (name "Net-(L2-Pad1)") (class "Default")
      (node (ref "L2") (pin "1") (pinfunction "1_1") (pintype "passive"))
      (node (ref "L3") (pin "2") (pinfunction "2_2") (pintype "passive"))
      (node (ref "U$15") (pin "ANT") (pinfunction "ANT_ANT") (pintype "bidirectional"))
    )
    (net (code "66") (name "Net-(LED1-PadA)") (class "Default")
      (node (ref "LED1") (pin "A") (pinfunction "A_A") (pintype "input"))
      (node (ref "R1") (pin "2") (pinfunction "2_2") (pintype "passive"))
    )
    (net (code "67") (name "Net-(LED2-PadA)") (class "Default")
      (node (ref "LED2") (pin "A") (pinfunction "A_A") (pintype "input"))
      (node (ref "R2") (pin "2") (pinfunction "2_2") (pintype "passive"))
    )
    (net (code "68") (name "Net-(LED3-PadA)") (class "Default")
      (node (ref "LED3") (pin "A") (pinfunction "A_A") (pintype "input"))
      (node (ref "R3") (pin "2") (pinfunction "2_2") (pintype "passive"))
    )
    (net (code "69") (name "Net-(LED4-PadA)") (class "Default")
      (node (ref "LED4") (pin "A") (pinfunction "A_A") (pintype "input"))
      (node (ref "R4") (pin "2") (pinfunction "2_2") (pintype "passive"))
    )
    (net (code "70") (name "Net-(LED5-PadA)") (class "Default")
      (node (ref "LED5") (pin "A") (pinfunction "A_A") (pintype "input"))
      (node (ref "R5") (pin "2") (pinfunction "2_2") (pintype "passive"))
    )
    (net (code "71") (name "Net-(LED6-PadA)") (class "Default")
      (node (ref "LED6") (pin "A") (pinfunction "A_A") (pintype "input"))
      (node (ref "R6") (pin "2") (pinfunction "2_2") (pintype "passive"))
    )
    (net (code "72") (name "Net-(LED7-PadA)") (class "Default")
      (node (ref "LED7") (pin "A") (pinfunction "A_A") (pintype "input"))
      (node (ref "R7") (pin "2") (pinfunction "2_2") (pintype "passive"))
    )
    (net (code "73") (name "Net-(LED8-PadA)") (class "Default")
      (node (ref "LED8") (pin "A") (pinfunction "A_A") (pintype "input"))
      (node (ref "R8") (pin "2") (pinfunction "2_2") (pintype "passive"))
    )
    (net (code "74") (name "Net-(LED9-PadA)") (class "Default")
      (node (ref "LED9") (pin "A") (pinfunction "A_A") (pintype "input"))
      (node (ref "R9") (pin "2") (pinfunction "2_2") (pintype "passive"))
    )
    (net (code "75") (name "Net-(LED10-PadA)") (class "Default")
      (node (ref "LED10") (pin "A") (pinfunction "A_A") (pintype "input"))
      (node (ref "R10") (pin "2") (pinfunction "2_2") (pintype "passive"))
    )
    (net (code "76") (name "Net-(LED11-PadA)") (class "Default")
      (node (ref "LED11") (pin "A") (pinfunction "A_A") (pintype "input"))
      (node (ref "R24") (pin "2") (pinfunction "2_2") (pintype "passive"))
    )
    (net (code "77") (name "Net-(LED12-PadA)") (class "Default")
      (node (ref "LED12") (pin "A") (pinfunction "A_A") (pintype "input"))
      (node (ref "R23") (pin "1") (pinfunction "1_1") (pintype "passive"))
    )
    (net (code "78") (name "Net-(LED13-PadA)") (class "Default")
      (node (ref "LED13") (pin "A") (pinfunction "A_A") (pintype "input"))
      (node (ref "R28") (pin "2") (pinfunction "2_2") (pintype "passive"))
    )
    (net (code "79") (name "Net-(R30-Pad1)") (class "Default")
      (node (ref "R30") (pin "1") (pinfunction "1_1") (pintype "passive"))
      (node (ref "R31") (pin "2") (pinfunction "2_2") (pintype "passive"))
      (node (ref "R33") (pin "2") (pinfunction "2_2") (pintype "passive"))
    )
    (net (code "80") (name "Net-(R31-Pad1)") (class "Default")
      (node (ref "R31") (pin "1") (pinfunction "1_1") (pintype "passive"))
      (node (ref "R32") (pin "2") (pinfunction "2_2") (pintype "passive"))
      (node (ref "R34") (pin "2") (pinfunction "2_2") (pintype "passive"))
    )
    (net (code "81") (name "Net-(TOUCH0-TOUCH)") (class "Default")
      (node (ref "R20") (pin "2") (pinfunction "2_2") (pintype "passive"))
      (node (ref "TOUCH0") (pin "PAD") (pinfunction "TOUCH_PAD") (pintype "bidirectional"))
    )
    (net (code "82") (name "Net-(TOUCH1-TOUCH)") (class "Default")
      (node (ref "R11") (pin "2") (pinfunction "2_2") (pintype "passive"))
      (node (ref "TOUCH1") (pin "PAD") (pinfunction "TOUCH_PAD") (pintype "bidirectional"))
    )
    (net (code "83") (name "Net-(TOUCH2-TOUCH)") (class "Default")
      (node (ref "R12") (pin "2") (pinfunction "2_2") (pintype "passive"))
      (node (ref "TOUCH2") (pin "PAD") (pinfunction "TOUCH_PAD") (pintype "bidirectional"))
    )
    (net (code "84") (name "Net-(TOUCH3-TOUCH)") (class "Default")
      (node (ref "R13") (pin "2") (pinfunction "2_2") (pintype "passive"))
      (node (ref "TOUCH3") (pin "PAD") (pinfunction "TOUCH_PAD") (pintype "bidirectional"))
    )
    (net (code "85") (name "Net-(TOUCH4-TOUCH)") (class "Default")
      (node (ref "R14") (pin "2") (pinfunction "2_2") (pintype "passive"))
      (node (ref "TOUCH4") (pin "PAD") (pinfunction "TOUCH_PAD") (pintype "bidirectional"))
    )
    (net (code "86") (name "Net-(TOUCH5-TOUCH)") (class "Default")
      (node (ref "R15") (pin "2") (pinfunction "2_2") (pintype "passive"))
      (node (ref "TOUCH5") (pin "PAD") (pinfunction "TOUCH_PAD") (pintype "bidirectional"))
    )
    (net (code "87") (name "Net-(TOUCH6-TOUCH)") (class "Default")
      (node (ref "R16") (pin "2") (pinfunction "2_2") (pintype "passive"))
      (node (ref "TOUCH6") (pin "PAD") (pinfunction "TOUCH_PAD") (pintype "bidirectional"))
    )
    (net (code "88") (name "Net-(TOUCH7-TOUCH)") (class "Default")
      (node (ref "R17") (pin "2") (pinfunction "2_2") (pintype "passive"))
      (node (ref "TOUCH7") (pin "PAD") (pinfunction "TOUCH_PAD") (pintype "bidirectional"))
    )
    (net (code "89") (name "Net-(TOUCH8-TOUCH)") (class "Default")
      (node (ref "R18") (pin "2") (pinfunction "2_2") (pintype "passive"))
      (node (ref "TOUCH8") (pin "PAD") (pinfunction "TOUCH_PAD") (pintype "bidirectional"))
    )
    (net (code "90") (name "Net-(TOUCH9-TOUCH)") (class "Default")
      (node (ref "R19") (pin "2") (pinfunction "2_2") (pintype "passive"))
      (node (ref "TOUCH9") (pin "PAD") (pinfunction "TOUCH_PAD") (pintype "bidirectional"))
    )
    (net (code "91") (name "Net-(TOUCHHOOK-TOUCH)") (class "Default")
      (node (ref "R21") (pin "2") (pinfunction "2_2") (pintype "passive"))
      (node (ref "TOUCHHOOK") (pin "P$1") (pinfunction "TOUCH_P$1") (pintype "bidirectional"))
    )
    (net (code "92") (name "Net-(U1-EN)") (class "Default")
      (node (ref "U$11") (pin "C") (pinfunction "C_C") (pintype "bidirectional"))
      (node (ref "U1") (pin "3") (pinfunction "EN_3") (pintype "bidirectional"))
    )
    (net (code "93") (name "Net-(U1-VIN)") (class "Default")
      (node (ref "F1") (pin "2") (pinfunction "2_2") (pintype "bidirectional"))
      (node (ref "U$11") (pin "2") (pinfunction "2_2") (pintype "bidirectional"))
      (node (ref "U1") (pin "1") (pinfunction "VIN_1") (pintype "bidirectional"))
    )
    (net (code "94") (name "Net-(U2-PROG)") (class "Default")
      (node (ref "R22") (pin "2") (pinfunction "2_2") (pintype "passive"))
      (node (ref "U2") (pin "5") (pinfunction "PROG_5") (pintype "bidirectional"))
    )
    (net (code "95") (name "Net-(U2-STAT)") (class "Default")
      (node (ref "LED12") (pin "C") (pinfunction "C_C") (pintype "output"))
      (node (ref "U2") (pin "1") (pinfunction "STAT_1") (pintype "bidirectional"))
    )
    (net (code "96") (name "VCC") (class "Default")
      (node (ref "C12") (pin "2") (pinfunction "2_2") (pintype "passive"))
      (node (ref "C13") (pin "2") (pinfunction "2_2") (pintype "passive"))
      (node (ref "C14") (pin "2") (pinfunction "2_2") (pintype "passive"))
      (node (ref "C15") (pin "2") (pinfunction "2_2") (pintype "passive"))
      (node (ref "C16") (pin "2") (pinfunction "2_2") (pintype "passive"))
      (node (ref "C21") (pin "2") (pinfunction "2_2") (pintype "passive"))
      (node (ref "R25") (pin "2") (pinfunction "2_2") (pintype "passive"))
      (node (ref "STLINK") (pin "VCC") (pinfunction "VCC_VCC") (pintype "power_in"))
      (node (ref "U$15") (pin "3.3V") (pinfunction "3.3V_3.3V") (pintype "bidirectional"))
      (node (ref "U$2") (pin "P13") (pinfunction "VDDA_P13") (pintype "bidirectional"))
      (node (ref "U$2") (pin "P19") (pinfunction "VDD4_P19") (pintype "bidirectional"))
      (node (ref "U$2") (pin "P32") (pinfunction "VDD1_P32") (pintype "bidirectional"))
      (node (ref "U$2") (pin "P48") (pinfunction "VDD2_P48") (pintype "bidirectional"))
      (node (ref "U$2") (pin "P64") (pinfunction "VDD3_P64") (pintype "bidirectional"))
      (node (ref "U$22") (pin "VCC") (pinfunction "VCC_VCC") (pintype "bidirectional"))
      (node (ref "U1") (pin "5") (pinfunction "VOUT_5") (pintype "bidirectional"))
      (node (ref "U3") (pin "2") (pinfunction "VS_2") (pintype "bidirectional"))
    )
    (net (code "97") (name "unconnected-(J1-ID-Pad4)") (class "Default")
      (node (ref "J1") (pin "4") (pinfunction "ID_4") (pintype "bidirectional"))
    )
    (net (code "98") (name "unconnected-(U$11-Pad1)") (class "Default")
      (node (ref "U$11") (pin "1") (pinfunction "1_1") (pintype "bidirectional"))
    )
    (net (code "99") (name "unconnected-(U$15-PadDIO2)") (class "Default")
      (node (ref "U$15") (pin "DIO2") (pinfunction "DIO2_DIO2") (pintype "bidirectional"))
    )
    (net (code "100") (name "unconnected-(U$15-PadDIO3)") (class "Default")
      (node (ref "U$15") (pin "DIO3") (pinfunction "DIO3_DIO3") (pintype "bidirectional"))
    )
    (net (code "101") (name "unconnected-(U$15-PadDIO4)") (class "Default")
      (node (ref "U$15") (pin "DIO4") (pinfunction "DIO4_DIO4") (pintype "bidirectional"))
    )
    (net (code "102") (name "unconnected-(U$15-PadDIO5)") (class "Default")
      (node (ref "U$15") (pin "DIO5") (pinfunction "DIO5_DIO5") (pintype "bidirectional"))
    )
  )
)
